# STM32_ADTDA.net
KiCad netlist of a schematic drawn in Altium Designer
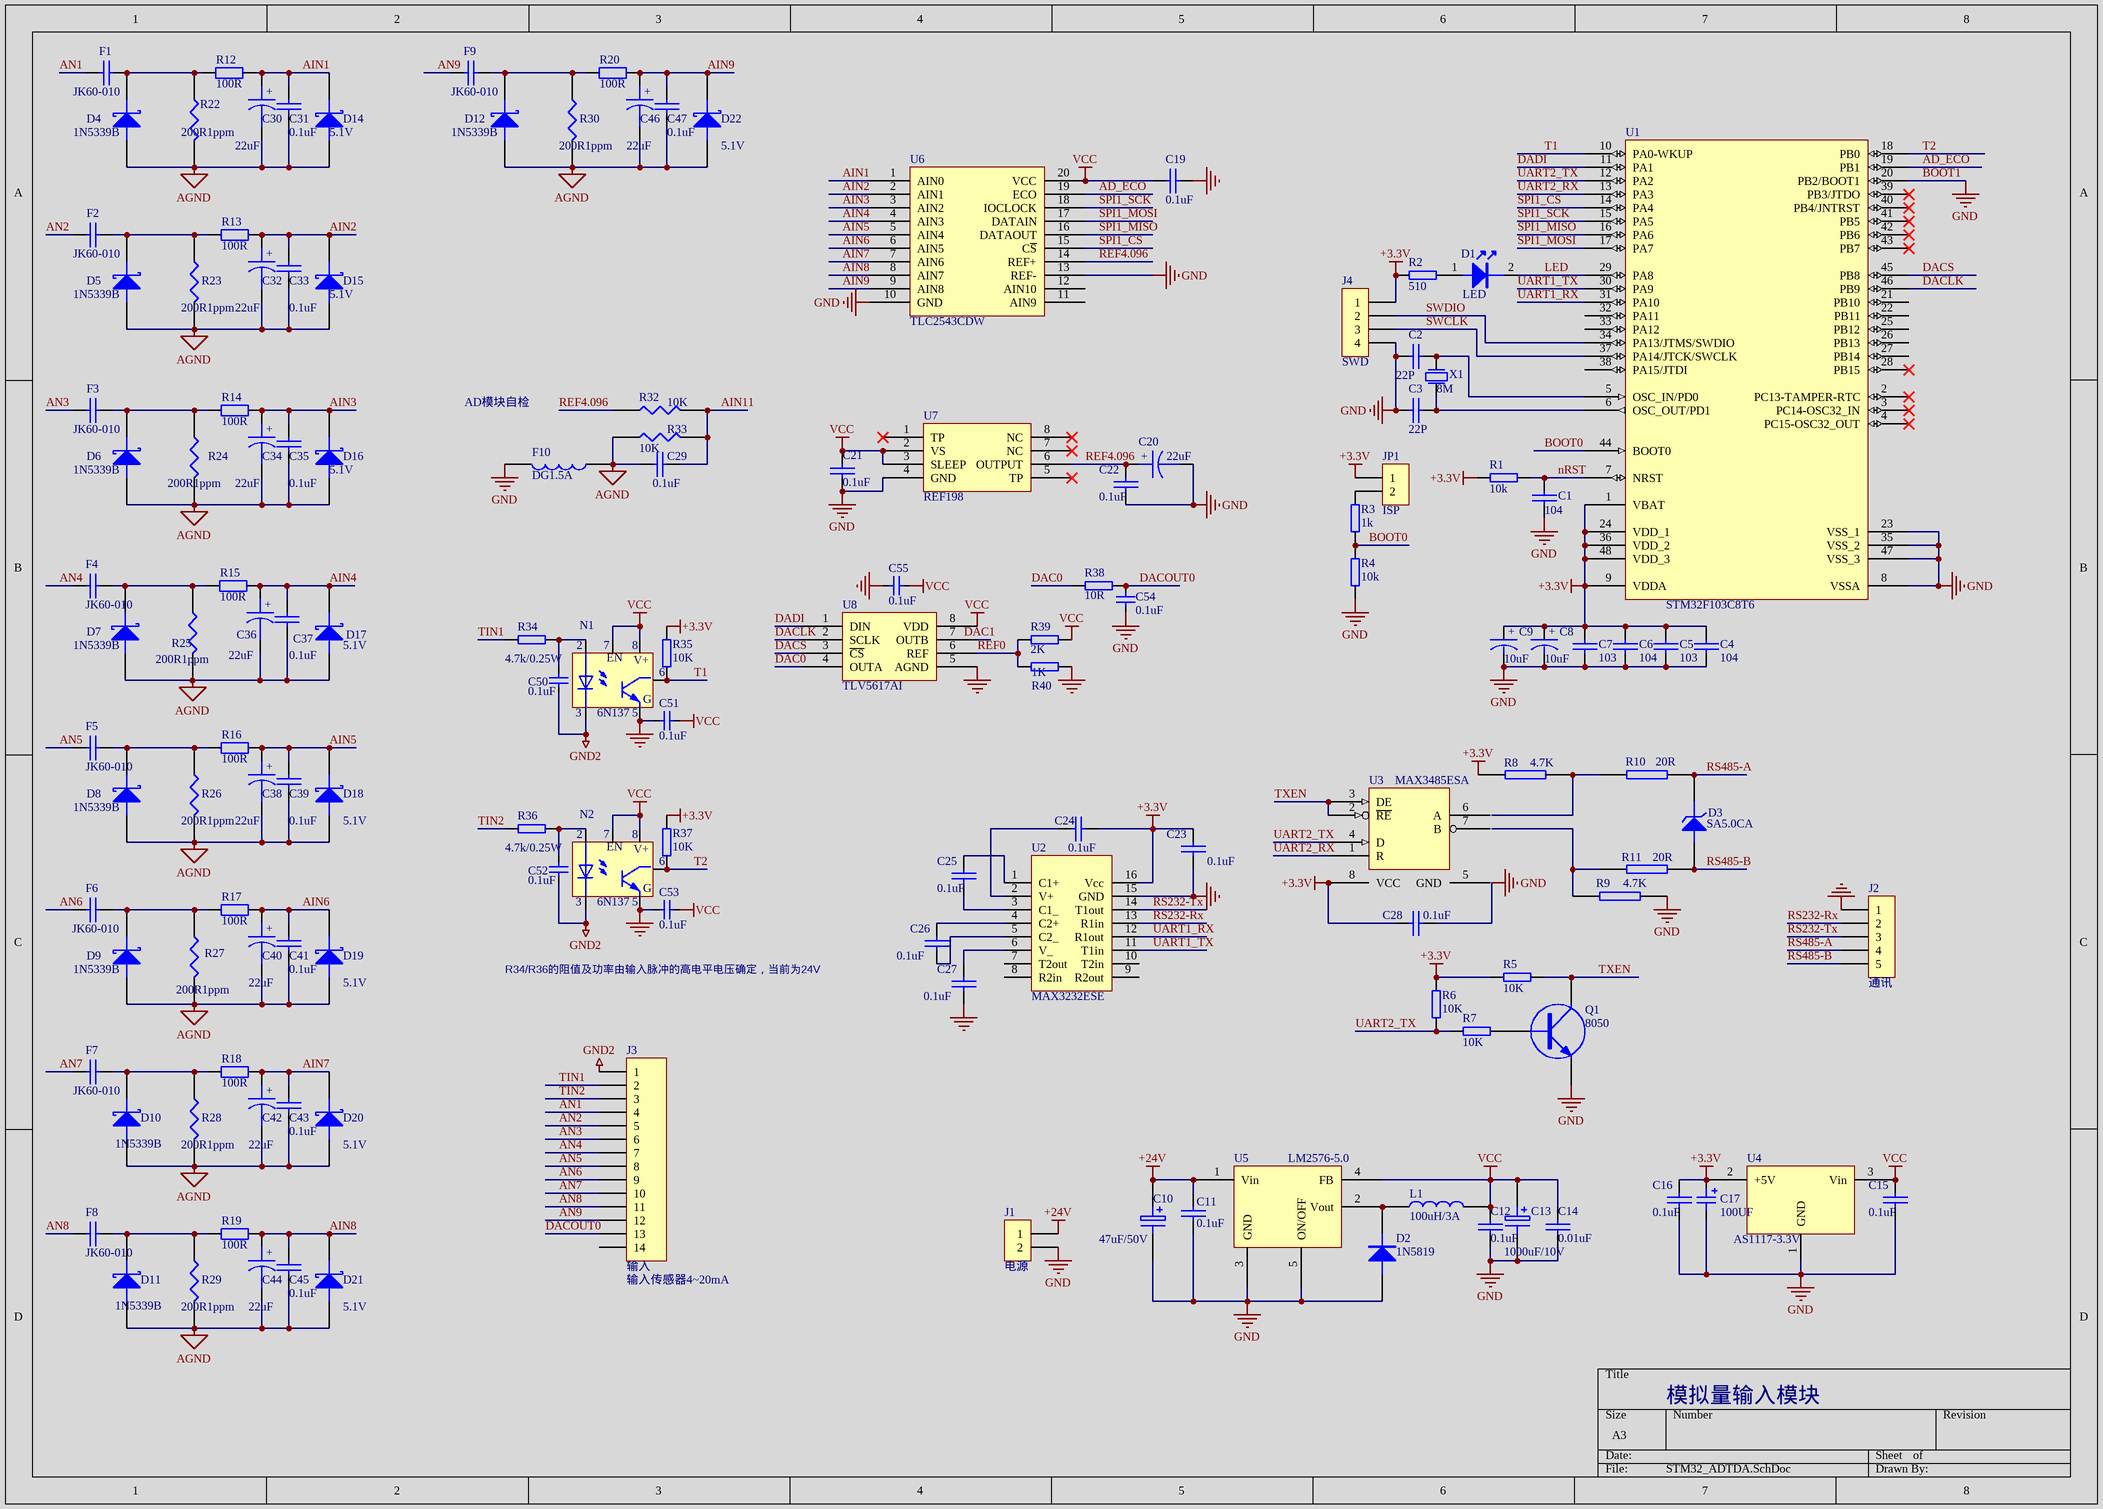
[diagram p0: STM32_ADTDA.SchDoc]

(export (version "E")
  (design (tool "Eeschema 10.0.6"))
  (components
    (comp (ref "C1")
      (value "104")
      (footprint "0805")
      (description "Capacitor")
      (libsource (lib "") (part "CAP_1"))
    )
    (comp (ref "C2")
      (value "22P")
      (footprint "0805")
      (description "Capacitor")
      (libsource (lib "*") (part "CAP"))
    )
    (comp (ref "C3")
      (value "22P")
      (footprint "0805")
      (description "Capacitor")
      (libsource (lib "*") (part "CAP"))
    )
    (comp (ref "C4")
      (value "104")
      (footprint "0805")
      (description "Capacitor")
      (libsource (lib "") (part "CAP_1"))
    )
    (comp (ref "C5")
      (value "103")
      (footprint "0805")
      (description "Capacitor")
      (libsource (lib "") (part "CAP_1"))
    )
    (comp (ref "C6")
      (value "104")
      (footprint "0805")
      (description "Capacitor")
      (libsource (lib "") (part "CAP_1"))
    )
    (comp (ref "C7")
      (value "103")
      (footprint "0805")
      (description "Capacitor")
      (libsource (lib "") (part "CAP_1"))
    )
    (comp (ref "C8")
      (value "10uF")
      (footprint "1210(+)")
      (description "Capacitor")
      (libsource (lib "2400原理图库") (part "CAPACITOR POL_1"))
    )
    (comp (ref "C9")
      (value "10uF")
      (footprint "1210(+)")
      (description "Capacitor")
      (libsource (lib "2400原理图库") (part "CAPACITOR POL_1"))
    )
    (comp (ref "C10")
      (value "47uF/50V")
      (footprint "ROND-0.2")
      (description "Electrolytic Capacitor")
      (libsource (lib "*") (part "ELECTRO1"))
    )
    (comp (ref "C11")
      (value "0.1uF")
      (footprint "0805")
      (description "Capacitor")
      (libsource (lib "") (part "CAP_2"))
    )
    (comp (ref "C12")
      (value "0.1uF")
      (footprint "0805")
      (description "Capacitor")
      (libsource (lib "") (part "CAP_2"))
    )
    (comp (ref "C13")
      (value "1000uF/10V")
      (footprint "DR10*10")
      (description "Electrolytic Capacitor")
      (libsource (lib "*") (part "ELECTRO1"))
    )
    (comp (ref "C14")
      (value "0.01uF")
      (footprint "0805")
      (description "Capacitor")
      (libsource (lib "") (part "CAP_2"))
    )
    (comp (ref "C15")
      (value "0.1uF")
      (footprint "0805")
      (description "Capacitor")
      (libsource (lib "*") (part "CAP"))
    )
    (comp (ref "C16")
      (value "0.1uF")
      (footprint "0805")
      (description "Capacitor")
      (libsource (lib "*") (part "CAP"))
    )
    (comp (ref "C17") (value "100UF") (footprint "2220-1") (libsource (lib "*") (part "CD")))
    (comp (ref "C19")
      (value "0.1uF")
      (footprint "0805")
      (description "Capacitor")
      (libsource (lib "*") (part "CAP"))
    )
    (comp (ref "C20")
      (value "22uF")
      (footprint "1210(+)")
      (description "Capacitor")
      (libsource (lib "*") (part "CAPACITOR POL"))
    )
    (comp (ref "C21")
      (value "0.1uF")
      (footprint "0805")
      (description "Capacitor")
      (libsource (lib "*") (part "CAP"))
    )
    (comp (ref "C22")
      (value "0.1uF")
      (footprint "0805")
      (description "Capacitor")
      (libsource (lib "*") (part "CAP"))
    )
    (comp (ref "C23")
      (value "0.1uF")
      (footprint "0805")
      (description "Capacitor")
      (libsource (lib "*") (part "CAP"))
    )
    (comp (ref "C24")
      (value "0.1uF")
      (footprint "0805")
      (description "Capacitor")
      (libsource (lib "*") (part "CAP"))
    )
    (comp (ref "C25")
      (value "0.1uF")
      (footprint "0805")
      (description "Capacitor")
      (libsource (lib "*") (part "CAP"))
    )
    (comp (ref "C26")
      (value "0.1uF")
      (footprint "0805")
      (description "Capacitor")
      (libsource (lib "*") (part "CAP"))
    )
    (comp (ref "C27")
      (value "0.1uF")
      (footprint "0805")
      (description "Capacitor")
      (libsource (lib "*") (part "CAP"))
    )
    (comp (ref "C28")
      (value "0.1uF")
      (footprint "0805")
      (description "Capacitor")
      (libsource (lib "*") (part "CAP"))
    )
    (comp (ref "C29")
      (value "0.1uF")
      (footprint "0805")
      (description "Capacitor")
      (libsource (lib "*") (part "CAP"))
    )
    (comp (ref "C30")
      (value "22uF")
      (footprint "1210(+)")
      (description "Capacitor")
      (libsource (lib "*") (part "CAPACITOR POL"))
    )
    (comp (ref "C31")
      (value "0.1uF")
      (footprint "0805")
      (description "Capacitor")
      (libsource (lib "*") (part "CAP"))
    )
    (comp (ref "C32")
      (value "22uF")
      (footprint "1210(+)")
      (description "Capacitor")
      (libsource (lib "*") (part "CAPACITOR POL"))
    )
    (comp (ref "C33")
      (value "0.1uF")
      (footprint "0805")
      (description "Capacitor")
      (libsource (lib "*") (part "CAP"))
    )
    (comp (ref "C34")
      (value "22uF")
      (footprint "1210(+)")
      (description "Capacitor")
      (libsource (lib "*") (part "CAPACITOR POL"))
    )
    (comp (ref "C35")
      (value "0.1uF")
      (footprint "0805")
      (description "Capacitor")
      (libsource (lib "*") (part "CAP"))
    )
    (comp (ref "C36")
      (value "22uF")
      (footprint "1210(+)")
      (description "Capacitor")
      (libsource (lib "*") (part "CAPACITOR POL"))
    )
    (comp (ref "C37")
      (value "0.1uF")
      (footprint "0805")
      (description "Capacitor")
      (libsource (lib "*") (part "CAP"))
    )
    (comp (ref "C38")
      (value "22uF")
      (footprint "1210(+)")
      (description "Capacitor")
      (libsource (lib "*") (part "CAPACITOR POL"))
    )
    (comp (ref "C39")
      (value "0.1uF")
      (footprint "0805")
      (description "Capacitor")
      (libsource (lib "*") (part "CAP"))
    )
    (comp (ref "C40")
      (value "22uF")
      (footprint "1210(+)")
      (description "Capacitor")
      (libsource (lib "*") (part "CAPACITOR POL"))
    )
    (comp (ref "C41")
      (value "0.1uF")
      (footprint "0805")
      (description "Capacitor")
      (libsource (lib "*") (part "CAP"))
    )
    (comp (ref "C42")
      (value "22uF")
      (footprint "1210(+)")
      (description "Capacitor")
      (libsource (lib "*") (part "CAPACITOR POL"))
    )
    (comp (ref "C43")
      (value "0.1uF")
      (footprint "0805")
      (description "Capacitor")
      (libsource (lib "*") (part "CAP"))
    )
    (comp (ref "C44")
      (value "22uF")
      (footprint "1210(+)")
      (description "Capacitor")
      (libsource (lib "*") (part "CAPACITOR POL"))
    )
    (comp (ref "C45")
      (value "0.1uF")
      (footprint "0805")
      (description "Capacitor")
      (libsource (lib "*") (part "CAP"))
    )
    (comp (ref "C46")
      (value "22uF")
      (footprint "1210(+)")
      (description "Capacitor")
      (libsource (lib "*") (part "CAPACITOR POL"))
    )
    (comp (ref "C47")
      (value "0.1uF")
      (footprint "0805")
      (description "Capacitor")
      (libsource (lib "*") (part "CAP"))
    )
    (comp (ref "C50") (value "0.1uF") (footprint "0805") (libsource (lib "*") (part "C")))
    (comp (ref "C51") (value "0.1uF") (footprint "0805") (libsource (lib "*") (part "C")))
    (comp (ref "C52") (value "0.1uF") (footprint "0805") (libsource (lib "*") (part "C")))
    (comp (ref "C53") (value "0.1uF") (footprint "0805") (libsource (lib "*") (part "C")))
    (comp (ref "C54") (value "0.1uF") (footprint "0805") (libsource (lib "*") (part "C")))
    (comp (ref "C55") (value "0.1uF") (footprint "0805") (libsource (lib "*") (part "C")))
    (comp (ref "D1") (value "LED") (footprint "ROND-0.2") (libsource (lib "pro1") (part "LED")))
    (comp (ref "D2")
      (value "1N5819")
      (footprint "DIODE-2")
      (description "Diode")
      (libsource (lib "*") (part "DIODE"))
    )
    (comp (ref "D3")
      (value "SA5.0CA")
      (footprint "CON2_4A7")
      (description "Zener Diode")
      (libsource (lib "*") (part "ZENER3"))
    )
    (comp (ref "D4")
      (value "1N5339B")
      (footprint "DIODE-0.3")
      (description "Schottky Diode")
      (libsource (lib "*") (part "DIODE SCHOTTKY"))
    )
    (comp (ref "D5")
      (value "1N5339B")
      (footprint "DIODE-0.3")
      (description "Schottky Diode")
      (libsource (lib "*") (part "DIODE SCHOTTKY"))
    )
    (comp (ref "D6")
      (value "1N5339B")
      (footprint "DIODE-0.3")
      (description "Schottky Diode")
      (libsource (lib "*") (part "DIODE SCHOTTKY"))
    )
    (comp (ref "D7")
      (value "1N5339B")
      (footprint "DIODE-0.3")
      (description "Schottky Diode")
      (libsource (lib "*") (part "DIODE SCHOTTKY"))
    )
    (comp (ref "D8")
      (value "1N5339B")
      (footprint "DIODE-0.3")
      (description "Schottky Diode")
      (libsource (lib "*") (part "DIODE SCHOTTKY"))
    )
    (comp (ref "D9")
      (value "1N5339B")
      (footprint "DIODE-0.3")
      (description "Schottky Diode")
      (libsource (lib "*") (part "DIODE SCHOTTKY"))
    )
    (comp (ref "D10")
      (value "1N5339B")
      (footprint "DIODE-0.3")
      (description "Schottky Diode")
      (libsource (lib "*") (part "DIODE SCHOTTKY"))
    )
    (comp (ref "D11")
      (value "1N5339B")
      (footprint "DIODE-0.3")
      (description "Schottky Diode")
      (libsource (lib "*") (part "DIODE SCHOTTKY"))
    )
    (comp (ref "D12")
      (value "1N5339B")
      (footprint "DIODE-0.3")
      (description "Schottky Diode")
      (libsource (lib "*") (part "DIODE SCHOTTKY"))
    )
    (comp (ref "D14")
      (value "5.1V")
      (footprint "DIDO")
      (description "Schottky Diode")
      (libsource (lib "*") (part "DIODE SCHOTTKY"))
    )
    (comp (ref "D15")
      (value "5.1V")
      (footprint "DIDO")
      (description "Schottky Diode")
      (libsource (lib "*") (part "DIODE SCHOTTKY"))
    )
    (comp (ref "D16")
      (value "5.1V")
      (footprint "DIDO")
      (description "Schottky Diode")
      (libsource (lib "*") (part "DIODE SCHOTTKY"))
    )
    (comp (ref "D17")
      (value "5.1V")
      (footprint "DIDO")
      (description "Schottky Diode")
      (libsource (lib "*") (part "DIODE SCHOTTKY"))
    )
    (comp (ref "D18")
      (value "5.1V")
      (footprint "DIDO")
      (description "Schottky Diode")
      (libsource (lib "*") (part "DIODE SCHOTTKY"))
    )
    (comp (ref "D19")
      (value "5.1V")
      (footprint "DIDO")
      (description "Schottky Diode")
      (libsource (lib "*") (part "DIODE SCHOTTKY"))
    )
    (comp (ref "D20")
      (value "5.1V")
      (footprint "DIDO")
      (description "Schottky Diode")
      (libsource (lib "*") (part "DIODE SCHOTTKY"))
    )
    (comp (ref "D21")
      (value "5.1V")
      (footprint "DIDO")
      (description "Schottky Diode")
      (libsource (lib "*") (part "DIODE SCHOTTKY"))
    )
    (comp (ref "D22")
      (value "5.1V")
      (footprint "DIDO")
      (description "Schottky Diode")
      (libsource (lib "*") (part "DIODE SCHOTTKY"))
    )
    (comp (ref "F1")
      (value "JK60-010")
      (footprint "RAD0.1")
      (description "Capacitor")
      (libsource (lib "*") (part "CAP"))
    )
    (comp (ref "F2")
      (value "JK60-010")
      (footprint "RAD0.1")
      (description "Capacitor")
      (libsource (lib "*") (part "CAP"))
    )
    (comp (ref "F3")
      (value "JK60-010")
      (footprint "RAD0.1")
      (description "Capacitor")
      (libsource (lib "*") (part "CAP"))
    )
    (comp (ref "F4")
      (value "JK60-010")
      (footprint "RAD0.1")
      (description "Capacitor")
      (libsource (lib "*") (part "CAP"))
    )
    (comp (ref "F5")
      (value "JK60-010")
      (footprint "RAD0.1")
      (description "Capacitor")
      (libsource (lib "*") (part "CAP"))
    )
    (comp (ref "F6")
      (value "JK60-010")
      (footprint "RAD0.1")
      (description "Capacitor")
      (libsource (lib "*") (part "CAP"))
    )
    (comp (ref "F7")
      (value "JK60-010")
      (footprint "RAD0.1")
      (description "Capacitor")
      (libsource (lib "*") (part "CAP"))
    )
    (comp (ref "F8")
      (value "JK60-010")
      (footprint "RAD0.1")
      (description "Capacitor")
      (libsource (lib "*") (part "CAP"))
    )
    (comp (ref "F9")
      (value "JK60-010")
      (footprint "RAD0.1")
      (description "Capacitor")
      (libsource (lib "*") (part "CAP"))
    )
    (comp (ref "F10") (value "DG1.5A") (footprint "0805") (libsource (lib "") (part "INDUCTOR1_1")))
    (comp (ref "J1")
      (value "电源")
      (footprint "CON2_5.08")
      (description "Connector")
      (libsource (lib "") (part "CON2_1"))
    )
    (comp (ref "J2")
      (value "通讯")
      (footprint "CON5_5.08")
      (description "Connector")
      (libsource (lib "pro1") (part "CON5"))
    )
    (comp (ref "J3") (value "输入") (libsource (lib "pro1") (part "CON14")))
    (comp (ref "J4")
      (value "SWD")
      (footprint "CON4_2")
      (description "Connector")
      (libsource (lib "*") (part "CON4"))
    )
    (comp (ref "JP1")
      (value "ISP")
      (footprint "CON2_2")
      (description "Connector")
      (libsource (lib "pro1") (part "CON2"))
    )
    (comp (ref "L1") (value "100uH/3A") (footprint "DIANGAN1.5A") (libsource (lib "*") (part "INDUCTOR1")))
    (comp (ref "N1") (value "6N137") (footprint "DIP8") (libsource (lib "*") (part "6N137")))
    (comp (ref "N2") (value "6N137") (footprint "DIP8") (libsource (lib "*") (part "6N137")))
    (comp (ref "Q1")
      (value "8050")
      (footprint "sot-23")
      (description "NPN Transistor")
      (libsource (lib "*") (part "NPN"))
    )
    (comp (ref "R1") (value "10k") (footprint "0805") (libsource (lib "") (part "RES1_1")))
    (comp (ref "R2") (value "510") (footprint "0805") (libsource (lib "") (part "RES1_1")))
    (comp (ref "R3") (value "1k") (footprint "0805") (libsource (lib "") (part "RES1_1")))
    (comp (ref "R4") (value "10k") (footprint "0805") (libsource (lib "") (part "RES1_1")))
    (comp (ref "R5") (value "10K") (footprint "0805") (libsource (lib "*") (part "R")))
    (comp (ref "R6") (value "10K") (footprint "0805") (libsource (lib "") (part "RES1_1")))
    (comp (ref "R7") (value "10K") (footprint "0805") (libsource (lib "*") (part "R")))
    (comp (ref "R8") (value "4.7K") (footprint "0805") (libsource (lib "*") (part "RES2")))
    (comp (ref "R9") (value "4.7K") (footprint "0805") (libsource (lib "*") (part "RES2")))
    (comp (ref "R10") (value "20R") (footprint "0805") (libsource (lib "*") (part "RES2")))
    (comp (ref "R11") (value "20R") (footprint "0805") (libsource (lib "*") (part "RES2")))
    (comp (ref "R12")
      (value "100R")
      (footprint "0805")
      (description "Resistor")
      (fields (field (name "PUBLISHER") "*"))
      (libsource (lib "*") (part "Res2"))
    )
    (comp (ref "R13")
      (value "100R")
      (footprint "0805")
      (description "Resistor")
      (fields (field (name "PUBLISHER") "*"))
      (libsource (lib "*") (part "Res2"))
    )
    (comp (ref "R14")
      (value "100R")
      (footprint "0805")
      (description "Resistor")
      (fields (field (name "PUBLISHER") "*"))
      (libsource (lib "*") (part "Res2"))
    )
    (comp (ref "R15")
      (value "100R")
      (footprint "0805")
      (description "Resistor")
      (fields (field (name "PUBLISHER") "*"))
      (libsource (lib "*") (part "Res2"))
    )
    (comp (ref "R16")
      (value "100R")
      (footprint "0805")
      (description "Resistor")
      (fields (field (name "PUBLISHER") "*"))
      (libsource (lib "*") (part "Res2"))
    )
    (comp (ref "R17")
      (value "100R")
      (footprint "0805")
      (description "Resistor")
      (fields (field (name "PUBLISHER") "*"))
      (libsource (lib "*") (part "Res2"))
    )
    (comp (ref "R18")
      (value "100R")
      (footprint "0805")
      (description "Resistor")
      (fields (field (name "PUBLISHER") "*"))
      (libsource (lib "*") (part "Res2"))
    )
    (comp (ref "R19")
      (value "100R")
      (footprint "0805")
      (description "Resistor")
      (fields (field (name "PUBLISHER") "*"))
      (libsource (lib "*") (part "Res2"))
    )
    (comp (ref "R20")
      (value "100R")
      (footprint "0805")
      (description "Resistor")
      (fields (field (name "PUBLISHER") "*"))
      (libsource (lib "*") (part "Res2"))
    )
    (comp (ref "R22") (value "200R1ppm") (footprint "axial0.3") (libsource (lib "*") (part "RES1")))
    (comp (ref "R23") (value "200R1ppm") (footprint "axial0.3") (libsource (lib "*") (part "RES1")))
    (comp (ref "R24") (value "200R1ppm") (footprint "axial0.3") (libsource (lib "*") (part "RES1")))
    (comp (ref "R25") (value "200R1ppm") (footprint "axial0.3") (libsource (lib "*") (part "RES1")))
    (comp (ref "R26") (value "200R1ppm") (footprint "axial0.3") (libsource (lib "*") (part "RES1")))
    (comp (ref "R27") (value "200R1ppm") (footprint "axial0.3") (libsource (lib "*") (part "RES1")))
    (comp (ref "R28") (value "200R1ppm") (footprint "axial0.3") (libsource (lib "*") (part "RES1")))
    (comp (ref "R29") (value "200R1ppm") (footprint "axial0.3") (libsource (lib "*") (part "RES1")))
    (comp (ref "R30") (value "200R1ppm") (footprint "axial0.3") (libsource (lib "*") (part "RES1")))
    (comp (ref "R32") (value "10K") (footprint "0805") (libsource (lib "*") (part "RES1")))
    (comp (ref "R33") (value "10K") (footprint "0805") (libsource (lib "*") (part "RES1")))
    (comp (ref "R34") (value "4.7k/0.25W") (footprint "1206") (libsource (lib "") (part "R_1")))
    (comp (ref "R35") (value "10K") (footprint "0805") (libsource (lib "") (part "R_1")))
    (comp (ref "R36") (value "4.7k/0.25W") (footprint "1206") (libsource (lib "") (part "R_1")))
    (comp (ref "R37") (value "10K") (footprint "0805") (libsource (lib "") (part "R_1")))
    (comp (ref "R38") (value "10R") (footprint "0805") (libsource (lib "") (part "R_1")))
    (comp (ref "R39") (value "2K") (footprint "0805") (libsource (lib "") (part "R_1")))
    (comp (ref "R40") (value "1K") (footprint "0805") (libsource (lib "") (part "R_1")))
    (comp (ref "U1")
      (value "STM32F103C8T6")
      (footprint "STM32F103C-48")
      (description "STM32 ARM-based 32-bit MCU with 64 Kbytes Flash, 48-pin LQFP, Industrial Temperature")
      (fields (field (name "PUBLISHER") "*"))
      (libsource (lib "ST Microcontroller 32-Bit STM32 SCH") (part "STM32F101C8T6"))
    )
    (comp (ref "U2")
      (value "MAX3232ESE")
      (footprint "SO-16")
      (description "Connector")
      (libsource (lib "*") (part "CON16"))
    )
    (comp (ref "U3")
      (value "MAX3485ESA")
      (footprint "SO-8")
      (description "DIFFERENTIAL BUS TRANSCEIVERS")
      (libsource (lib "*") (part "DS36F95"))
    )
    (comp (ref "U4") (value "AS1117-3.3V") (footprint "sot223") (libsource (lib "*") (part "MC79L05CG")))
    (comp (ref "U5") (value "LM2576-5.0") (footprint "TO-220-5S") (libsource (lib "*") (part "LM2576")))
    (comp (ref "U6") (value "TLC2543CDW") (footprint "SOL-20") (libsource (lib "*") (part "TCL2543")))
    (comp (ref "U7") (value "REF198") (footprint "SO-8") (libsource (lib "*") (part "Component_1")))
    (comp (ref "U8") (value "TLV5617AI") (footprint "SO-8") (libsource (lib "*") (part "TLV5617A")))
    (comp (ref "X1")
      (value "8M")
      (footprint "XATL-5MM")
      (description "Crystal Oscillator")
      (libsource (lib "*") (part "12M"))
    )
  )
  (nets
    (net (code "1") (name "+3.3V") (class "Default")
      (node (ref "C12") (pin "1") (pinfunction "1_1") (pintype "passive"))
      (node (ref "C13") (pin "1") (pinfunction "1_1") (pintype "passive"))
      (node (ref "C14") (pin "2") (pinfunction "2_2") (pintype "passive"))
      (node (ref "C15") (pin "2") (pinfunction "2_2") (pintype "passive"))
      (node (ref "C16") (pin "2") (pinfunction "2_2") (pintype "passive"))
      (node (ref "C17") (pin "1") (pintype "passive"))
      (node (ref "C19") (pin "1") (pinfunction "1_1") (pintype "passive"))
      (node (ref "C21") (pin "1") (pinfunction "1_1") (pintype "passive"))
      (node (ref "C23") (pin "1") (pinfunction "1_1") (pintype "passive"))
      (node (ref "C24") (pin "2") (pinfunction "2_2") (pintype "passive"))
      (node (ref "C28") (pin "1") (pinfunction "1_1") (pintype "passive"))
      (node (ref "C4") (pin "1") (pinfunction "1_1") (pintype "passive"))
      (node (ref "C5") (pin "1") (pinfunction "1_1") (pintype "passive"))
      (node (ref "C51") (pin "1") (pintype "passive"))
      (node (ref "C53") (pin "1") (pintype "passive"))
      (node (ref "C55") (pin "1") (pintype "passive"))
      (node (ref "C6") (pin "1") (pinfunction "1_1") (pintype "passive"))
      (node (ref "C7") (pin "1") (pinfunction "1_1") (pintype "passive"))
      (node (ref "C8") (pin "1") (pinfunction "1_1") (pintype "passive"))
      (node (ref "C9") (pin "1") (pinfunction "1_1") (pintype "passive"))
      (node (ref "J4") (pin "1") (pinfunction "1_1") (pintype "passive"))
      (node (ref "JP1") (pin "1") (pinfunction "1_1") (pintype "passive"))
      (node (ref "L1") (pin "2") (pinfunction "2_2") (pintype "passive"))
      (node (ref "N1") (pin "7") (pinfunction "EN_7") (pintype "passive"))
      (node (ref "N1") (pin "8") (pinfunction "VCC_8") (pintype "passive"))
      (node (ref "N2") (pin "7") (pinfunction "EN_7") (pintype "passive"))
      (node (ref "N2") (pin "8") (pinfunction "VCC_8") (pintype "passive"))
      (node (ref "R1") (pin "1") (pintype "passive"))
      (node (ref "R2") (pin "1") (pintype "passive"))
      (node (ref "R35") (pin "2") (pintype "passive"))
      (node (ref "R37") (pin "2") (pintype "passive"))
      (node (ref "R39") (pin "1") (pintype "passive"))
      (node (ref "R5") (pin "1") (pintype "passive"))
      (node (ref "R6") (pin "1") (pintype "passive"))
      (node (ref "R8") (pin "2") (pinfunction "2_2") (pintype "passive"))
      (node (ref "U1") (pin "1") (pinfunction "VBAT_1") (pintype "power_in"))
      (node (ref "U1") (pin "24") (pinfunction "VDD_1_24") (pintype "power_in"))
      (node (ref "U1") (pin "36") (pinfunction "VDD_2_36") (pintype "power_in"))
      (node (ref "U1") (pin "48") (pinfunction "VDD_3_48") (pintype "power_in"))
      (node (ref "U1") (pin "9") (pinfunction "VDDA_9") (pintype "power_in"))
      (node (ref "U2") (pin "16") (pinfunction "Vcc_16") (pintype "passive"))
      (node (ref "U3") (pin "8") (pinfunction "VCC_8") (pintype "power_in"))
      (node (ref "U4") (pin "2") (pinfunction "+5V_2") (pintype "passive"))
      (node (ref "U4") (pin "3") (pinfunction "Vin_3") (pintype "passive"))
      (node (ref "U5") (pin "4") (pinfunction "FB_4") (pintype "passive"))
      (node (ref "U6") (pin "20") (pinfunction "VCC_20") (pintype "passive"))
      (node (ref "U7") (pin "2") (pinfunction "VS_2") (pintype "passive"))
      (node (ref "U7") (pin "3") (pinfunction "SLEEP_3") (pintype "passive"))
      (node (ref "U8") (pin "8") (pinfunction "VDD_8") (pintype "passive"))
    )
    (net (code "2") (name "+24V") (class "Default")
      (node (ref "C10") (pin "1") (pinfunction "1_1") (pintype "passive"))
      (node (ref "C11") (pin "2") (pinfunction "2_2") (pintype "passive"))
      (node (ref "J1") (pin "1") (pinfunction "1_1") (pintype "passive"))
      (node (ref "U5") (pin "1") (pinfunction "Vin_1") (pintype "passive"))
    )
    (net (code "3") (name "/AD_ECO") (class "Default")
      (node (ref "U1") (pin "19") (pinfunction "PB1_19") (pintype "bidirectional"))
      (node (ref "U6") (pin "19") (pinfunction "ECO_19") (pintype "passive"))
    )
    (net (code "4") (name "/AIN1") (class "Default")
      (node (ref "C30") (pin "1") (pinfunction "1_1") (pintype "passive"))
      (node (ref "C31") (pin "1") (pinfunction "1_1") (pintype "passive"))
      (node (ref "D14") (pin "2") (pinfunction "K_2") (pintype "passive"))
      (node (ref "R12") (pin "2") (pinfunction "2_2") (pintype "passive"))
      (node (ref "U6") (pin "1") (pinfunction "AIN0_1") (pintype "passive"))
    )
    (net (code "5") (name "/AIN2") (class "Default")
      (node (ref "C32") (pin "1") (pinfunction "1_1") (pintype "passive"))
      (node (ref "C33") (pin "1") (pinfunction "1_1") (pintype "passive"))
      (node (ref "D15") (pin "2") (pinfunction "K_2") (pintype "passive"))
      (node (ref "R13") (pin "2") (pinfunction "2_2") (pintype "passive"))
      (node (ref "U6") (pin "2") (pinfunction "AIN1_2") (pintype "passive"))
    )
    (net (code "6") (name "/AIN3") (class "Default")
      (node (ref "C34") (pin "1") (pinfunction "1_1") (pintype "passive"))
      (node (ref "C35") (pin "1") (pinfunction "1_1") (pintype "passive"))
      (node (ref "D16") (pin "2") (pinfunction "K_2") (pintype "passive"))
      (node (ref "R14") (pin "2") (pinfunction "2_2") (pintype "passive"))
      (node (ref "U6") (pin "3") (pinfunction "AIN2_3") (pintype "passive"))
    )
    (net (code "7") (name "/AIN4") (class "Default")
      (node (ref "C36") (pin "1") (pinfunction "1_1") (pintype "passive"))
      (node (ref "C37") (pin "1") (pinfunction "1_1") (pintype "passive"))
      (node (ref "D17") (pin "2") (pinfunction "K_2") (pintype "passive"))
      (node (ref "R15") (pin "2") (pinfunction "2_2") (pintype "passive"))
      (node (ref "U6") (pin "4") (pinfunction "AIN3_4") (pintype "passive"))
    )
    (net (code "8") (name "/AIN5") (class "Default")
      (node (ref "C38") (pin "1") (pinfunction "1_1") (pintype "passive"))
      (node (ref "C39") (pin "1") (pinfunction "1_1") (pintype "passive"))
      (node (ref "D18") (pin "2") (pinfunction "K_2") (pintype "passive"))
      (node (ref "R16") (pin "2") (pinfunction "2_2") (pintype "passive"))
      (node (ref "U6") (pin "5") (pinfunction "AIN4_5") (pintype "passive"))
    )
    (net (code "9") (name "/AIN6") (class "Default")
      (node (ref "C40") (pin "1") (pinfunction "1_1") (pintype "passive"))
      (node (ref "C41") (pin "1") (pinfunction "1_1") (pintype "passive"))
      (node (ref "D19") (pin "2") (pinfunction "K_2") (pintype "passive"))
      (node (ref "R17") (pin "2") (pinfunction "2_2") (pintype "passive"))
      (node (ref "U6") (pin "6") (pinfunction "AIN5_6") (pintype "passive"))
    )
    (net (code "10") (name "/AIN7") (class "Default")
      (node (ref "C42") (pin "1") (pinfunction "1_1") (pintype "passive"))
      (node (ref "C43") (pin "1") (pinfunction "1_1") (pintype "passive"))
      (node (ref "D20") (pin "2") (pinfunction "K_2") (pintype "passive"))
      (node (ref "R18") (pin "2") (pinfunction "2_2") (pintype "passive"))
      (node (ref "U6") (pin "7") (pinfunction "AIN6_7") (pintype "passive"))
    )
    (net (code "11") (name "/AIN8") (class "Default")
      (node (ref "C44") (pin "1") (pinfunction "1_1") (pintype "passive"))
      (node (ref "C45") (pin "1") (pinfunction "1_1") (pintype "passive"))
      (node (ref "D21") (pin "2") (pinfunction "K_2") (pintype "passive"))
      (node (ref "R19") (pin "2") (pinfunction "2_2") (pintype "passive"))
      (node (ref "U6") (pin "8") (pinfunction "AIN7_8") (pintype "passive"))
    )
    (net (code "12") (name "/AIN9") (class "Default")
      (node (ref "C46") (pin "1") (pinfunction "1_1") (pintype "passive"))
      (node (ref "C47") (pin "1") (pinfunction "1_1") (pintype "passive"))
      (node (ref "D22") (pin "2") (pinfunction "K_2") (pintype "passive"))
      (node (ref "R20") (pin "2") (pinfunction "2_2") (pintype "passive"))
      (node (ref "U6") (pin "9") (pinfunction "AIN8_9") (pintype "passive"))
    )
    (net (code "13") (name "/AIN11") (class "Default")
      (node (ref "C29") (pin "2") (pinfunction "2_2") (pintype "passive"))
      (node (ref "R32") (pin "2") (pinfunction "2_2") (pintype "passive"))
      (node (ref "R33") (pin "2") (pinfunction "2_2") (pintype "passive"))
    )
    (net (code "14") (name "/AN1") (class "Default")
      (node (ref "F1") (pin "1") (pinfunction "1_1") (pintype "passive"))
      (node (ref "J3") (pin "4") (pinfunction "4_4") (pintype "passive"))
    )
    (net (code "15") (name "/AN2") (class "Default")
      (node (ref "F2") (pin "1") (pinfunction "1_1") (pintype "passive"))
      (node (ref "J3") (pin "5") (pinfunction "5_5") (pintype "passive"))
    )
    (net (code "16") (name "/AN3") (class "Default")
      (node (ref "F3") (pin "1") (pinfunction "1_1") (pintype "passive"))
      (node (ref "J3") (pin "6") (pinfunction "6_6") (pintype "passive"))
    )
    (net (code "17") (name "/AN4") (class "Default")
      (node (ref "F4") (pin "1") (pinfunction "1_1") (pintype "passive"))
      (node (ref "J3") (pin "7") (pinfunction "7_7") (pintype "passive"))
    )
    (net (code "18") (name "/AN5") (class "Default")
      (node (ref "F5") (pin "1") (pinfunction "1_1") (pintype "passive"))
      (node (ref "J3") (pin "8") (pinfunction "8_8") (pintype "passive"))
    )
    (net (code "19") (name "/AN6") (class "Default")
      (node (ref "F6") (pin "1") (pinfunction "1_1") (pintype "passive"))
      (node (ref "J3") (pin "9") (pinfunction "9_9") (pintype "passive"))
    )
    (net (code "20") (name "/AN7") (class "Default")
      (node (ref "F7") (pin "1") (pinfunction "1_1") (pintype "passive"))
      (node (ref "J3") (pin "10") (pinfunction "10_10") (pintype "passive"))
    )
    (net (code "21") (name "/AN8") (class "Default")
      (node (ref "F8") (pin "1") (pinfunction "1_1") (pintype "passive"))
      (node (ref "J3") (pin "11") (pinfunction "11_11") (pintype "passive"))
    )
    (net (code "22") (name "/AN9") (class "Default")
      (node (ref "F9") (pin "1") (pinfunction "1_1") (pintype "passive"))
      (node (ref "J3") (pin "12") (pinfunction "12_12") (pintype "passive"))
    )
    (net (code "23") (name "/BOOT0") (class "Default")
      (node (ref "R3") (pin "2") (pintype "passive"))
      (node (ref "R4") (pin "1") (pintype "passive"))
      (node (ref "U1") (pin "44") (pinfunction "BOOT0_44") (pintype "input"))
    )
    (net (code "24") (name "/DAC0") (class "Default")
      (node (ref "R38") (pin "2") (pintype "passive"))
      (node (ref "U8") (pin "4") (pinfunction "OUTA_4") (pintype "passive"))
    )
    (net (code "26") (name "/DACLK") (class "Default")
      (node (ref "U1") (pin "46") (pinfunction "PB9_46") (pintype "bidirectional"))
      (node (ref "U8") (pin "2") (pinfunction "SCLK_2") (pintype "passive"))
    )
    (net (code "27") (name "/DACOUT0") (class "Default")
      (node (ref "C54") (pin "1") (pintype "passive"))
      (node (ref "J3") (pin "13") (pinfunction "13_13") (pintype "passive"))
      (node (ref "R38") (pin "1") (pintype "passive"))
    )
    (net (code "28") (name "/DACS") (class "Default")
      (node (ref "U1") (pin "45") (pinfunction "PB8_45") (pintype "bidirectional"))
      (node (ref "U8") (pin "3") (pinfunction "~{CS}_3") (pintype "passive"))
    )
    (net (code "29") (name "/DADI") (class "Default")
      (node (ref "U1") (pin "11") (pinfunction "PA1_11") (pintype "bidirectional"))
      (node (ref "U8") (pin "1") (pinfunction "DIN_1") (pintype "passive"))
    )
    (net (code "30") (name "/LED") (class "Default")
      (node (ref "D1") (pin "2") (pinfunction "K_2") (pintype "passive"))
      (node (ref "U1") (pin "29") (pinfunction "PA8_29") (pintype "bidirectional"))
    )
    (net (code "31") (name "/REF0") (class "Default")
      (node (ref "R39") (pin "2") (pintype "passive"))
      (node (ref "R40") (pin "2") (pintype "passive"))
      (node (ref "U8") (pin "6") (pinfunction "REF_6") (pintype "passive"))
    )
    (net (code "32") (name "/REF4.096") (class "Default")
      (node (ref "C20") (pin "1") (pinfunction "1_1") (pintype "passive"))
      (node (ref "C22") (pin "1") (pinfunction "1_1") (pintype "passive"))
      (node (ref "R32") (pin "1") (pinfunction "1_1") (pintype "passive"))
      (node (ref "U6") (pin "14") (pinfunction "REF+_14") (pintype "passive"))
      (node (ref "U7") (pin "6") (pinfunction "OUTPUT_6") (pintype "passive"))
    )
    (net (code "33") (name "/RS232-Rx") (class "Default")
      (node (ref "J2") (pin "2") (pinfunction "2_2") (pintype "passive"))
      (node (ref "U2") (pin "13") (pinfunction "R1in_13") (pintype "passive"))
    )
    (net (code "34") (name "/RS232-Tx") (class "Default")
      (node (ref "J2") (pin "3") (pinfunction "3_3") (pintype "passive"))
      (node (ref "U2") (pin "14") (pinfunction "T1out_14") (pintype "passive"))
    )
    (net (code "35") (name "/RS485-A") (class "Default")
      (node (ref "D3") (pin "2") (pinfunction "K_2") (pintype "passive"))
      (node (ref "J2") (pin "4") (pinfunction "4_4") (pintype "passive"))
      (node (ref "R10") (pin "2") (pinfunction "2_2") (pintype "passive"))
    )
    (net (code "36") (name "/RS485-B") (class "Default")
      (node (ref "D3") (pin "1") (pinfunction "A_1") (pintype "passive"))
      (node (ref "J2") (pin "5") (pinfunction "5_5") (pintype "passive"))
      (node (ref "R11") (pin "2") (pinfunction "2_2") (pintype "passive"))
    )
    (net (code "37") (name "/SPI1_CS") (class "Default")
      (node (ref "U1") (pin "14") (pinfunction "PA4_14") (pintype "bidirectional"))
      (node (ref "U6") (pin "15") (pinfunction "C~{S}_15") (pintype "passive"))
    )
    (net (code "38") (name "/SPI1_MISO") (class "Default")
      (node (ref "U1") (pin "16") (pinfunction "PA6_16") (pintype "bidirectional"))
      (node (ref "U6") (pin "16") (pinfunction "DATAOUT_16") (pintype "passive"))
    )
    (net (code "39") (name "/SPI1_MOSI") (class "Default")
      (node (ref "U1") (pin "17") (pinfunction "PA7_17") (pintype "bidirectional"))
      (node (ref "U6") (pin "17") (pinfunction "DATAIN_17") (pintype "passive"))
    )
    (net (code "40") (name "/SPI1_SCK") (class "Default")
      (node (ref "U1") (pin "15") (pinfunction "PA5_15") (pintype "bidirectional"))
      (node (ref "U6") (pin "18") (pinfunction "IOCLOCK_18") (pintype "passive"))
    )
    (net (code "41") (name "/SWCLK") (class "Default")
      (node (ref "J4") (pin "3") (pinfunction "3_3") (pintype "passive"))
      (node (ref "U1") (pin "37") (pinfunction "PA14/JTCK/SWCLK_37") (pintype "bidirectional"))
    )
    (net (code "42") (name "/SWDIO") (class "Default")
      (node (ref "J4") (pin "2") (pinfunction "2_2") (pintype "passive"))
      (node (ref "U1") (pin "34") (pinfunction "PA13/JTMS/SWDIO_34") (pintype "bidirectional"))
    )
    (net (code "43") (name "/T1") (class "Default")
      (node (ref "N1") (pin "6") (pinfunction "OUT_6") (pintype "passive"))
      (node (ref "R35") (pin "1") (pintype "passive"))
      (node (ref "U1") (pin "10") (pinfunction "PA0-WKUP_10") (pintype "bidirectional"))
    )
    (net (code "44") (name "/T2") (class "Default")
      (node (ref "N2") (pin "6") (pinfunction "OUT_6") (pintype "passive"))
      (node (ref "R37") (pin "1") (pintype "passive"))
      (node (ref "U1") (pin "18") (pinfunction "PB0_18") (pintype "bidirectional"))
    )
    (net (code "45") (name "/TIN1") (class "Default")
      (node (ref "J3") (pin "2") (pinfunction "2_2") (pintype "passive"))
      (node (ref "R34") (pin "2") (pintype "passive"))
    )
    (net (code "46") (name "/TIN2") (class "Default")
      (node (ref "J3") (pin "3") (pinfunction "3_3") (pintype "passive"))
      (node (ref "R36") (pin "2") (pintype "passive"))
    )
    (net (code "47") (name "/TXEN") (class "Default")
      (node (ref "Q1") (pin "3") (pinfunction "C_3") (pintype "passive"))
      (node (ref "R5") (pin "2") (pintype "passive"))
      (node (ref "U3") (pin "2") (pinfunction "~{RE}_2") (pintype "input"))
      (node (ref "U3") (pin "3") (pinfunction "DE_3") (pintype "input"))
    )
    (net (code "48") (name "/UART1_RX") (class "Default")
      (node (ref "U1") (pin "31") (pinfunction "PA10_31") (pintype "bidirectional"))
      (node (ref "U2") (pin "12") (pinfunction "R1out_12") (pintype "passive"))
    )
    (net (code "49") (name "/UART1_TX") (class "Default")
      (node (ref "U1") (pin "30") (pinfunction "PA9_30") (pintype "bidirectional"))
      (node (ref "U2") (pin "11") (pinfunction "T1in_11") (pintype "passive"))
    )
    (net (code "50") (name "/UART2_RX") (class "Default")
      (node (ref "U1") (pin "13") (pinfunction "PA3_13") (pintype "bidirectional"))
      (node (ref "U3") (pin "1") (pinfunction "R_1") (pintype "tri_state"))
    )
    (net (code "51") (name "/UART2_TX") (class "Default")
      (node (ref "R6") (pin "2") (pintype "passive"))
      (node (ref "R7") (pin "1") (pintype "passive"))
      (node (ref "U1") (pin "12") (pinfunction "PA2_12") (pintype "bidirectional"))
      (node (ref "U3") (pin "4") (pinfunction "D_4") (pintype "input"))
    )
    (net (code "52") (name "/nRST") (class "Default")
      (node (ref "C1") (pin "2") (pinfunction "2_2") (pintype "passive"))
      (node (ref "R1") (pin "2") (pintype "passive"))
      (node (ref "U1") (pin "7") (pinfunction "NRST_7") (pintype "bidirectional"))
    )
    (net (code "53") (name "AGND") (class "Default")
      (node (ref "C29") (pin "1") (pinfunction "1_1") (pintype "passive"))
      (node (ref "C30") (pin "2") (pinfunction "2_2") (pintype "passive"))
      (node (ref "C31") (pin "2") (pinfunction "2_2") (pintype "passive"))
      (node (ref "C32") (pin "2") (pinfunction "2_2") (pintype "passive"))
      (node (ref "C33") (pin "2") (pinfunction "2_2") (pintype "passive"))
      (node (ref "C34") (pin "2") (pinfunction "2_2") (pintype "passive"))
      (node (ref "C35") (pin "2") (pinfunction "2_2") (pintype "passive"))
      (node (ref "C36") (pin "2") (pinfunction "2_2") (pintype "passive"))
      (node (ref "C37") (pin "2") (pinfunction "2_2") (pintype "passive"))
      (node (ref "C38") (pin "2") (pinfunction "2_2") (pintype "passive"))
      (node (ref "C39") (pin "2") (pinfunction "2_2") (pintype "passive"))
      (node (ref "C40") (pin "2") (pinfunction "2_2") (pintype "passive"))
      (node (ref "C41") (pin "2") (pinfunction "2_2") (pintype "passive"))
      (node (ref "C42") (pin "2") (pinfunction "2_2") (pintype "passive"))
      (node (ref "C43") (pin "2") (pinfunction "2_2") (pintype "passive"))
      (node (ref "C44") (pin "2") (pinfunction "2_2") (pintype "passive"))
      (node (ref "C45") (pin "2") (pinfunction "2_2") (pintype "passive"))
      (node (ref "C46") (pin "2") (pinfunction "2_2") (pintype "passive"))
      (node (ref "C47") (pin "2") (pinfunction "2_2") (pintype "passive"))
      (node (ref "D10") (pin "1") (pinfunction "A_1") (pintype "passive"))
      (node (ref "D11") (pin "1") (pinfunction "A_1") (pintype "passive"))
      (node (ref "D12") (pin "1") (pinfunction "A_1") (pintype "passive"))
      (node (ref "D14") (pin "1") (pinfunction "A_1") (pintype "passive"))
      (node (ref "D15") (pin "1") (pinfunction "A_1") (pintype "passive"))
      (node (ref "D16") (pin "1") (pinfunction "A_1") (pintype "passive"))
      (node (ref "D17") (pin "1") (pinfunction "A_1") (pintype "passive"))
      (node (ref "D18") (pin "1") (pinfunction "A_1") (pintype "passive"))
      (node (ref "D19") (pin "1") (pinfunction "A_1") (pintype "passive"))
      (node (ref "D20") (pin "1") (pinfunction "A_1") (pintype "passive"))
      (node (ref "D21") (pin "1") (pinfunction "A_1") (pintype "passive"))
      (node (ref "D22") (pin "1") (pinfunction "A_1") (pintype "passive"))
      (node (ref "D4") (pin "1") (pinfunction "A_1") (pintype "passive"))
      (node (ref "D5") (pin "1") (pinfunction "A_1") (pintype "passive"))
      (node (ref "D6") (pin "1") (pinfunction "A_1") (pintype "passive"))
      (node (ref "D7") (pin "1") (pinfunction "A_1") (pintype "passive"))
      (node (ref "D8") (pin "1") (pinfunction "A_1") (pintype "passive"))
      (node (ref "D9") (pin "1") (pinfunction "A_1") (pintype "passive"))
      (node (ref "F10") (pin "1") (pinfunction "1_1") (pintype "passive"))
      (node (ref "R22") (pin "2") (pinfunction "2_2") (pintype "passive"))
      (node (ref "R23") (pin "2") (pinfunction "2_2") (pintype "passive"))
      (node (ref "R24") (pin "2") (pinfunction "2_2") (pintype "passive"))
      (node (ref "R25") (pin "2") (pinfunction "2_2") (pintype "passive"))
      (node (ref "R26") (pin "2") (pinfunction "2_2") (pintype "passive"))
      (node (ref "R27") (pin "2") (pinfunction "2_2") (pintype "passive"))
      (node (ref "R28") (pin "2") (pinfunction "2_2") (pintype "passive"))
      (node (ref "R29") (pin "2") (pinfunction "2_2") (pintype "passive"))
      (node (ref "R30") (pin "2") (pinfunction "2_2") (pintype "passive"))
      (node (ref "R33") (pin "1") (pinfunction "1_1") (pintype "passive"))
    )
    (net (code "54") (name "GND") (class "Default")
      (node (ref "C1") (pin "1") (pinfunction "1_1") (pintype "passive"))
      (node (ref "C10") (pin "2") (pinfunction "2_2") (pintype "passive"))
      (node (ref "C11") (pin "1") (pinfunction "1_1") (pintype "passive"))
      (node (ref "C12") (pin "2") (pinfunction "2_2") (pintype "passive"))
      (node (ref "C13") (pin "2") (pinfunction "2_2") (pintype "passive"))
      (node (ref "C14") (pin "1") (pinfunction "1_1") (pintype "passive"))
      (node (ref "C15") (pin "1") (pinfunction "1_1") (pintype "passive"))
      (node (ref "C16") (pin "1") (pinfunction "1_1") (pintype "passive"))
      (node (ref "C17") (pin "2") (pintype "passive"))
      (node (ref "C19") (pin "2") (pinfunction "2_2") (pintype "passive"))
      (node (ref "C2") (pin "1") (pinfunction "1_1") (pintype "passive"))
      (node (ref "C20") (pin "2") (pinfunction "2_2") (pintype "passive"))
      (node (ref "C21") (pin "2") (pinfunction "2_2") (pintype "passive"))
      (node (ref "C22") (pin "2") (pinfunction "2_2") (pintype "passive"))
      (node (ref "C23") (pin "2") (pinfunction "2_2") (pintype "passive"))
      (node (ref "C27") (pin "1") (pinfunction "1_1") (pintype "passive"))
      (node (ref "C28") (pin "2") (pinfunction "2_2") (pintype "passive"))
      (node (ref "C3") (pin "1") (pinfunction "1_1") (pintype "passive"))
      (node (ref "C4") (pin "2") (pinfunction "2_2") (pintype "passive"))
      (node (ref "C5") (pin "2") (pinfunction "2_2") (pintype "passive"))
      (node (ref "C51") (pin "2") (pintype "passive"))
      (node (ref "C53") (pin "2") (pintype "passive"))
      (node (ref "C54") (pin "2") (pintype "passive"))
      (node (ref "C55") (pin "2") (pintype "passive"))
      (node (ref "C6") (pin "2") (pinfunction "2_2") (pintype "passive"))
      (node (ref "C7") (pin "2") (pinfunction "2_2") (pintype "passive"))
      (node (ref "C8") (pin "2") (pinfunction "2_2") (pintype "passive"))
      (node (ref "C9") (pin "2") (pinfunction "2_2") (pintype "passive"))
      (node (ref "D2") (pin "1") (pinfunction "A_1") (pintype "passive"))
      (node (ref "F10") (pin "2") (pinfunction "2_2") (pintype "passive"))
      (node (ref "J1") (pin "2") (pinfunction "2_2") (pintype "passive"))
      (node (ref "J2") (pin "1") (pinfunction "1_1") (pintype "passive"))
      (node (ref "J4") (pin "4") (pinfunction "4_4") (pintype "passive"))
      (node (ref "N1") (pin "5") (pinfunction "GND_5") (pintype "passive"))
      (node (ref "N2") (pin "5") (pinfunction "GND_5") (pintype "passive"))
      (node (ref "Q1") (pin "2") (pinfunction "E_2") (pintype "passive"))
      (node (ref "R4") (pin "2") (pintype "passive"))
      (node (ref "R40") (pin "1") (pintype "passive"))
      (node (ref "R9") (pin "2") (pinfunction "2_2") (pintype "passive"))
      (node (ref "U1") (pin "20") (pinfunction "PB2/BOOT1_20") (pintype "bidirectional"))
      (node (ref "U1") (pin "23") (pinfunction "VSS_1_23") (pintype "power_in"))
      (node (ref "U1") (pin "35") (pinfunction "VSS_2_35") (pintype "power_in"))
      (node (ref "U1") (pin "47") (pinfunction "VSS_3_47") (pintype "power_in"))
      (node (ref "U1") (pin "8") (pinfunction "VSSA_8") (pintype "power_in"))
      (node (ref "U2") (pin "15") (pinfunction "GND_15") (pintype "passive"))
      (node (ref "U3") (pin "5") (pinfunction "GND_5") (pintype "power_in"))
      (node (ref "U4") (pin "1") (pinfunction "GND_1") (pintype "passive"))
      (node (ref "U5") (pin "3") (pinfunction "GND_3") (pintype "passive"))
      (node (ref "U5") (pin "5") (pinfunction "ON/OFF_5") (pintype "passive"))
      (node (ref "U6") (pin "10") (pinfunction "GND_10") (pintype "passive"))
      (node (ref "U6") (pin "13") (pinfunction "REF-_13") (pintype "passive"))
      (node (ref "U7") (pin "4") (pinfunction "GND_4") (pintype "passive"))
      (node (ref "U8") (pin "5") (pinfunction "AGND_5") (pintype "passive"))
    )
    (net (code "55") (name "GND2") (class "Default")
      (node (ref "C50") (pin "1") (pintype "passive"))
      (node (ref "C52") (pin "1") (pintype "passive"))
      (node (ref "J3") (pin "1") (pinfunction "1_1") (pintype "passive"))
      (node (ref "N1") (pin "3") (pinfunction "K_3") (pintype "passive"))
      (node (ref "N2") (pin "3") (pinfunction "K_3") (pintype "passive"))
    )
    (net (code "56") (name "Net-(D1-A)") (class "Default")
      (node (ref "D1") (pin "1") (pinfunction "A_1") (pintype "passive"))
      (node (ref "R2") (pin "2") (pintype "passive"))
    )
    (net (code "57") (name "Net-(D2-K)") (class "Default")
      (node (ref "D2") (pin "2") (pinfunction "K_2") (pintype "passive"))
      (node (ref "L1") (pin "1") (pinfunction "1_1") (pintype "passive"))
      (node (ref "U5") (pin "2") (pinfunction "Vout_2") (pintype "passive"))
    )
    (net (code "58") (name "Net-(D4-K)") (class "Default")
      (node (ref "D4") (pin "2") (pinfunction "K_2") (pintype "passive"))
      (node (ref "F1") (pin "2") (pinfunction "2_2") (pintype "passive"))
      (node (ref "R12") (pin "1") (pinfunction "1_1") (pintype "passive"))
      (node (ref "R22") (pin "1") (pinfunction "1_1") (pintype "passive"))
    )
    (net (code "59") (name "Net-(D5-K)") (class "Default")
      (node (ref "D5") (pin "2") (pinfunction "K_2") (pintype "passive"))
      (node (ref "F2") (pin "2") (pinfunction "2_2") (pintype "passive"))
      (node (ref "R13") (pin "1") (pinfunction "1_1") (pintype "passive"))
      (node (ref "R23") (pin "1") (pinfunction "1_1") (pintype "passive"))
    )
    (net (code "60") (name "Net-(D6-K)") (class "Default")
      (node (ref "D6") (pin "2") (pinfunction "K_2") (pintype "passive"))
      (node (ref "F3") (pin "2") (pinfunction "2_2") (pintype "passive"))
      (node (ref "R14") (pin "1") (pinfunction "1_1") (pintype "passive"))
      (node (ref "R24") (pin "1") (pinfunction "1_1") (pintype "passive"))
    )
    (net (code "61") (name "Net-(D7-K)") (class "Default")
      (node (ref "D7") (pin "2") (pinfunction "K_2") (pintype "passive"))
      (node (ref "F4") (pin "2") (pinfunction "2_2") (pintype "passive"))
      (node (ref "R15") (pin "1") (pinfunction "1_1") (pintype "passive"))
      (node (ref "R25") (pin "1") (pinfunction "1_1") (pintype "passive"))
    )
    (net (code "62") (name "Net-(D8-K)") (class "Default")
      (node (ref "D8") (pin "2") (pinfunction "K_2") (pintype "passive"))
      (node (ref "F5") (pin "2") (pinfunction "2_2") (pintype "passive"))
      (node (ref "R16") (pin "1") (pinfunction "1_1") (pintype "passive"))
      (node (ref "R26") (pin "1") (pinfunction "1_1") (pintype "passive"))
    )
    (net (code "63") (name "Net-(D9-K)") (class "Default")
      (node (ref "D9") (pin "2") (pinfunction "K_2") (pintype "passive"))
      (node (ref "F6") (pin "2") (pinfunction "2_2") (pintype "passive"))
      (node (ref "R17") (pin "1") (pinfunction "1_1") (pintype "passive"))
      (node (ref "R27") (pin "1") (pinfunction "1_1") (pintype "passive"))
    )
    (net (code "64") (name "Net-(D10-K)") (class "Default")
      (node (ref "D10") (pin "2") (pinfunction "K_2") (pintype "passive"))
      (node (ref "F7") (pin "2") (pinfunction "2_2") (pintype "passive"))
      (node (ref "R18") (pin "1") (pinfunction "1_1") (pintype "passive"))
      (node (ref "R28") (pin "1") (pinfunction "1_1") (pintype "passive"))
    )
    (net (code "65") (name "Net-(D11-K)") (class "Default")
      (node (ref "D11") (pin "2") (pinfunction "K_2") (pintype "passive"))
      (node (ref "F8") (pin "2") (pinfunction "2_2") (pintype "passive"))
      (node (ref "R19") (pin "1") (pinfunction "1_1") (pintype "passive"))
      (node (ref "R29") (pin "1") (pinfunction "1_1") (pintype "passive"))
    )
    (net (code "66") (name "Net-(D12-K)") (class "Default")
      (node (ref "D12") (pin "2") (pinfunction "K_2") (pintype "passive"))
      (node (ref "F9") (pin "2") (pinfunction "2_2") (pintype "passive"))
      (node (ref "R20") (pin "1") (pinfunction "1_1") (pintype "passive"))
      (node (ref "R30") (pin "1") (pinfunction "1_1") (pintype "passive"))
    )
    (net (code "67") (name "Net-(JP1-Pad2)") (class "Default")
      (node (ref "JP1") (pin "2") (pinfunction "2_2") (pintype "passive"))
      (node (ref "R3") (pin "1") (pintype "passive"))
    )
    (net (code "68") (name "Net-(N1-A)") (class "Default")
      (node (ref "C50") (pin "2") (pintype "passive"))
      (node (ref "N1") (pin "2") (pinfunction "A_2") (pintype "passive"))
      (node (ref "R34") (pin "1") (pintype "passive"))
    )
    (net (code "69") (name "Net-(N2-A)") (class "Default")
      (node (ref "C52") (pin "2") (pintype "passive"))
      (node (ref "N2") (pin "2") (pinfunction "A_2") (pintype "passive"))
      (node (ref "R36") (pin "1") (pintype "passive"))
    )
    (net (code "70") (name "Net-(Q1-B)") (class "Default")
      (node (ref "Q1") (pin "1") (pinfunction "B_1") (pintype "passive"))
      (node (ref "R7") (pin "2") (pintype "passive"))
    )
    (net (code "71") (name "Net-(R10-Pad1)") (class "Default")
      (node (ref "R10") (pin "1") (pinfunction "1_1") (pintype "passive"))
      (node (ref "R8") (pin "1") (pinfunction "1_1") (pintype "passive"))
    )
    (net (code "72") (name "Net-(R11-Pad1)") (class "Default")
      (node (ref "R11") (pin "1") (pinfunction "1_1") (pintype "passive"))
      (node (ref "R9") (pin "1") (pinfunction "1_1") (pintype "passive"))
    )
    (net (code "73") (name "Net-(U1-OSC_IN{slash}PD0)") (class "Default")
      (node (ref "C2") (pin "2") (pinfunction "2_2") (pintype "passive"))
      (node (ref "U1") (pin "5") (pinfunction "OSC_IN/PD0_5") (pintype "input"))
      (node (ref "X1") (pin "2") (pinfunction "P2_2") (pintype "passive"))
    )
    (net (code "74") (name "Net-(U1-OSC_OUT{slash}PD1)") (class "Default")
      (node (ref "C3") (pin "2") (pinfunction "2_2") (pintype "passive"))
      (node (ref "U1") (pin "6") (pinfunction "OSC_OUT/PD1_6") (pintype "output"))
      (node (ref "X1") (pin "1") (pinfunction "P1_1") (pintype "passive"))
    )
    (net (code "75") (name "Net-(U2-C1+)") (class "Default")
      (node (ref "C25") (pin "1") (pinfunction "1_1") (pintype "passive"))
      (node (ref "U2") (pin "1") (pinfunction "C1+_1") (pintype "passive"))
    )
    (net (code "76") (name "Net-(U2-C1_)") (class "Default")
      (node (ref "C25") (pin "2") (pinfunction "2_2") (pintype "passive"))
      (node (ref "U2") (pin "3") (pinfunction "C1__3") (pintype "passive"))
    )
    (net (code "77") (name "Net-(U2-C2+)") (class "Default")
      (node (ref "C26") (pin "1") (pinfunction "1_1") (pintype "passive"))
      (node (ref "U2") (pin "4") (pinfunction "C2+_4") (pintype "passive"))
    )
    (net (code "78") (name "Net-(U2-C2_)") (class "Default")
      (node (ref "C26") (pin "2") (pinfunction "2_2") (pintype "passive"))
      (node (ref "U2") (pin "5") (pinfunction "C2__5") (pintype "passive"))
    )
    (net (code "79") (name "Net-(U2-V+)") (class "Default")
      (node (ref "C24") (pin "1") (pinfunction "1_1") (pintype "passive"))
      (node (ref "U2") (pin "2") (pinfunction "V+_2") (pintype "passive"))
    )
    (net (code "80") (name "Net-(U2-V_)") (class "Default")
      (node (ref "C27") (pin "2") (pinfunction "2_2") (pintype "passive"))
      (node (ref "U2") (pin "6") (pinfunction "V__6") (pintype "passive"))
    )
    (net (code "81") (name "unconnected-(J3-Pad14)") (class "Default")
      (node (ref "J3") (pin "14") (pinfunction "14_14") (pintype "passive"))
    )
    (net (code "82") (name "unconnected-(U1-PA11-Pad32)") (class "Default")
      (node (ref "U1") (pin "32") (pinfunction "PA11_32") (pintype "bidirectional"))
    )
    (net (code "83") (name "unconnected-(U1-PA12-Pad33)") (class "Default")
      (node (ref "U1") (pin "33") (pinfunction "PA12_33") (pintype "bidirectional"))
    )
    (net (code "84") (name "unconnected-(U1-PA15{slash}JTDI-Pad38)") (class "Default")
      (node (ref "U1") (pin "38") (pinfunction "PA15/JTDI_38") (pintype "bidirectional"))
    )
    (net (code "85") (name "unconnected-(U1-PB3{slash}JTDO-Pad39)") (class "Default")
      (node (ref "U1") (pin "39") (pinfunction "PB3/JTDO_39") (pintype "bidirectional+no_connect"))
    )
    (net (code "86") (name "unconnected-(U1-PB4{slash}JNTRST-Pad40)") (class "Default")
      (node (ref "U1") (pin "40") (pinfunction "PB4/JNTRST_40") (pintype "bidirectional+no_connect"))
    )
    (net (code "87") (name "unconnected-(U1-PB5-Pad41)") (class "Default")
      (node (ref "U1") (pin "41") (pinfunction "PB5_41") (pintype "bidirectional+no_connect"))
    )
    (net (code "88") (name "unconnected-(U1-PB6-Pad42)") (class "Default")
      (node (ref "U1") (pin "42") (pinfunction "PB6_42") (pintype "bidirectional+no_connect"))
    )
    (net (code "89") (name "unconnected-(U1-PB7-Pad43)") (class "Default")
      (node (ref "U1") (pin "43") (pinfunction "PB7_43") (pintype "bidirectional+no_connect"))
    )
    (net (code "90") (name "unconnected-(U1-PB10-Pad21)") (class "Default")
      (node (ref "U1") (pin "21") (pinfunction "PB10_21") (pintype "bidirectional"))
    )
    (net (code "91") (name "unconnected-(U1-PB11-Pad22)") (class "Default")
      (node (ref "U1") (pin "22") (pinfunction "PB11_22") (pintype "bidirectional"))
    )
    (net (code "92") (name "unconnected-(U1-PB12-Pad25)") (class "Default")
      (node (ref "U1") (pin "25") (pinfunction "PB12_25") (pintype "bidirectional"))
    )
    (net (code "93") (name "unconnected-(U1-PB13-Pad26)") (class "Default")
      (node (ref "U1") (pin "26") (pinfunction "PB13_26") (pintype "bidirectional"))
    )
    (net (code "94") (name "unconnected-(U1-PB14-Pad27)") (class "Default")
      (node (ref "U1") (pin "27") (pinfunction "PB14_27") (pintype "bidirectional"))
    )
    (net (code "95") (name "unconnected-(U1-PB15-Pad28)") (class "Default")
      (node (ref "U1") (pin "28") (pinfunction "PB15_28") (pintype "bidirectional+no_connect"))
    )
    (net (code "96") (name "unconnected-(U1-PC13-TAMPER-RTC-Pad2)") (class "Default")
      (node (ref "U1") (pin "2") (pinfunction "PC13-TAMPER-RTC_2") (pintype "bidirectional+no_connect"))
    )
    (net (code "97") (name "unconnected-(U1-PC14-OSC32_IN-Pad3)") (class "Default")
      (node (ref "U1") (pin "3") (pinfunction "PC14-OSC32_IN_3") (pintype "bidirectional+no_connect"))
    )
    (net (code "98") (name "unconnected-(U1-PC15-OSC32_OUT-Pad4)") (class "Default")
      (node (ref "U1") (pin "4") (pinfunction "PC15-OSC32_OUT_4") (pintype "bidirectional+no_connect"))
    )
    (net (code "99") (name "unconnected-(U2-R2in-Pad8)") (class "Default")
      (node (ref "U2") (pin "8") (pinfunction "R2in_8") (pintype "passive"))
    )
    (net (code "100") (name "unconnected-(U2-R2out-Pad9)") (class "Default")
      (node (ref "U2") (pin "9") (pinfunction "R2out_9") (pintype "passive"))
    )
    (net (code "101") (name "unconnected-(U2-T2in-Pad10)") (class "Default")
      (node (ref "U2") (pin "10") (pinfunction "T2in_10") (pintype "passive"))
    )
    (net (code "102") (name "unconnected-(U2-T2out-Pad7)") (class "Default")
      (node (ref "U2") (pin "7") (pinfunction "T2out_7") (pintype "passive"))
    )
    (net (code "103") (name "unconnected-(U3-A-Pad6)") (class "Default")
      (node (ref "U3") (pin "6") (pinfunction "A_6") (pintype "tri_state"))
    )
    (net (code "104") (name "unconnected-(U3-B-Pad7)") (class "Default")
      (node (ref "U3") (pin "7") (pinfunction "B_7") (pintype "tri_state"))
    )
    (net (code "105") (name "unconnected-(U6-AIN9-Pad11)") (class "Default")
      (node (ref "U6") (pin "11") (pinfunction "AIN9_11") (pintype "passive"))
    )
    (net (code "106") (name "unconnected-(U6-AIN10-Pad12)") (class "Default")
      (node (ref "U6") (pin "12") (pinfunction "AIN10_12") (pintype "passive"))
    )
    (net (code "107") (name "unconnected-(U7-NC-Pad7)") (class "Default")
      (node (ref "U7") (pin "7") (pinfunction "NC_7") (pintype "passive+no_connect"))
    )
    (net (code "108") (name "unconnected-(U7-NC-Pad8)") (class "Default")
      (node (ref "U7") (pin "8") (pinfunction "NC_8") (pintype "passive+no_connect"))
    )
    (net (code "109") (name "unconnected-(U7-TP-Pad1)") (class "Default")
      (node (ref "U7") (pin "1") (pinfunction "TP_1") (pintype "passive+no_connect"))
    )
    (net (code "110") (name "unconnected-(U7-TP-Pad5)") (class "Default")
      (node (ref "U7") (pin "5") (pinfunction "TP_5") (pintype "passive+no_connect"))
    )
    (net (code "111") (name "unconnected-(U8-OUTB-Pad7)") (class "Default")
      (node (ref "U8") (pin "7") (pinfunction "OUTB_7") (pintype "passive"))
    )
  )
)
